# SCH_RP2040-sussybaka_2024-10-22.net
KiCad netlist of a schematic drawn in EasyEDA
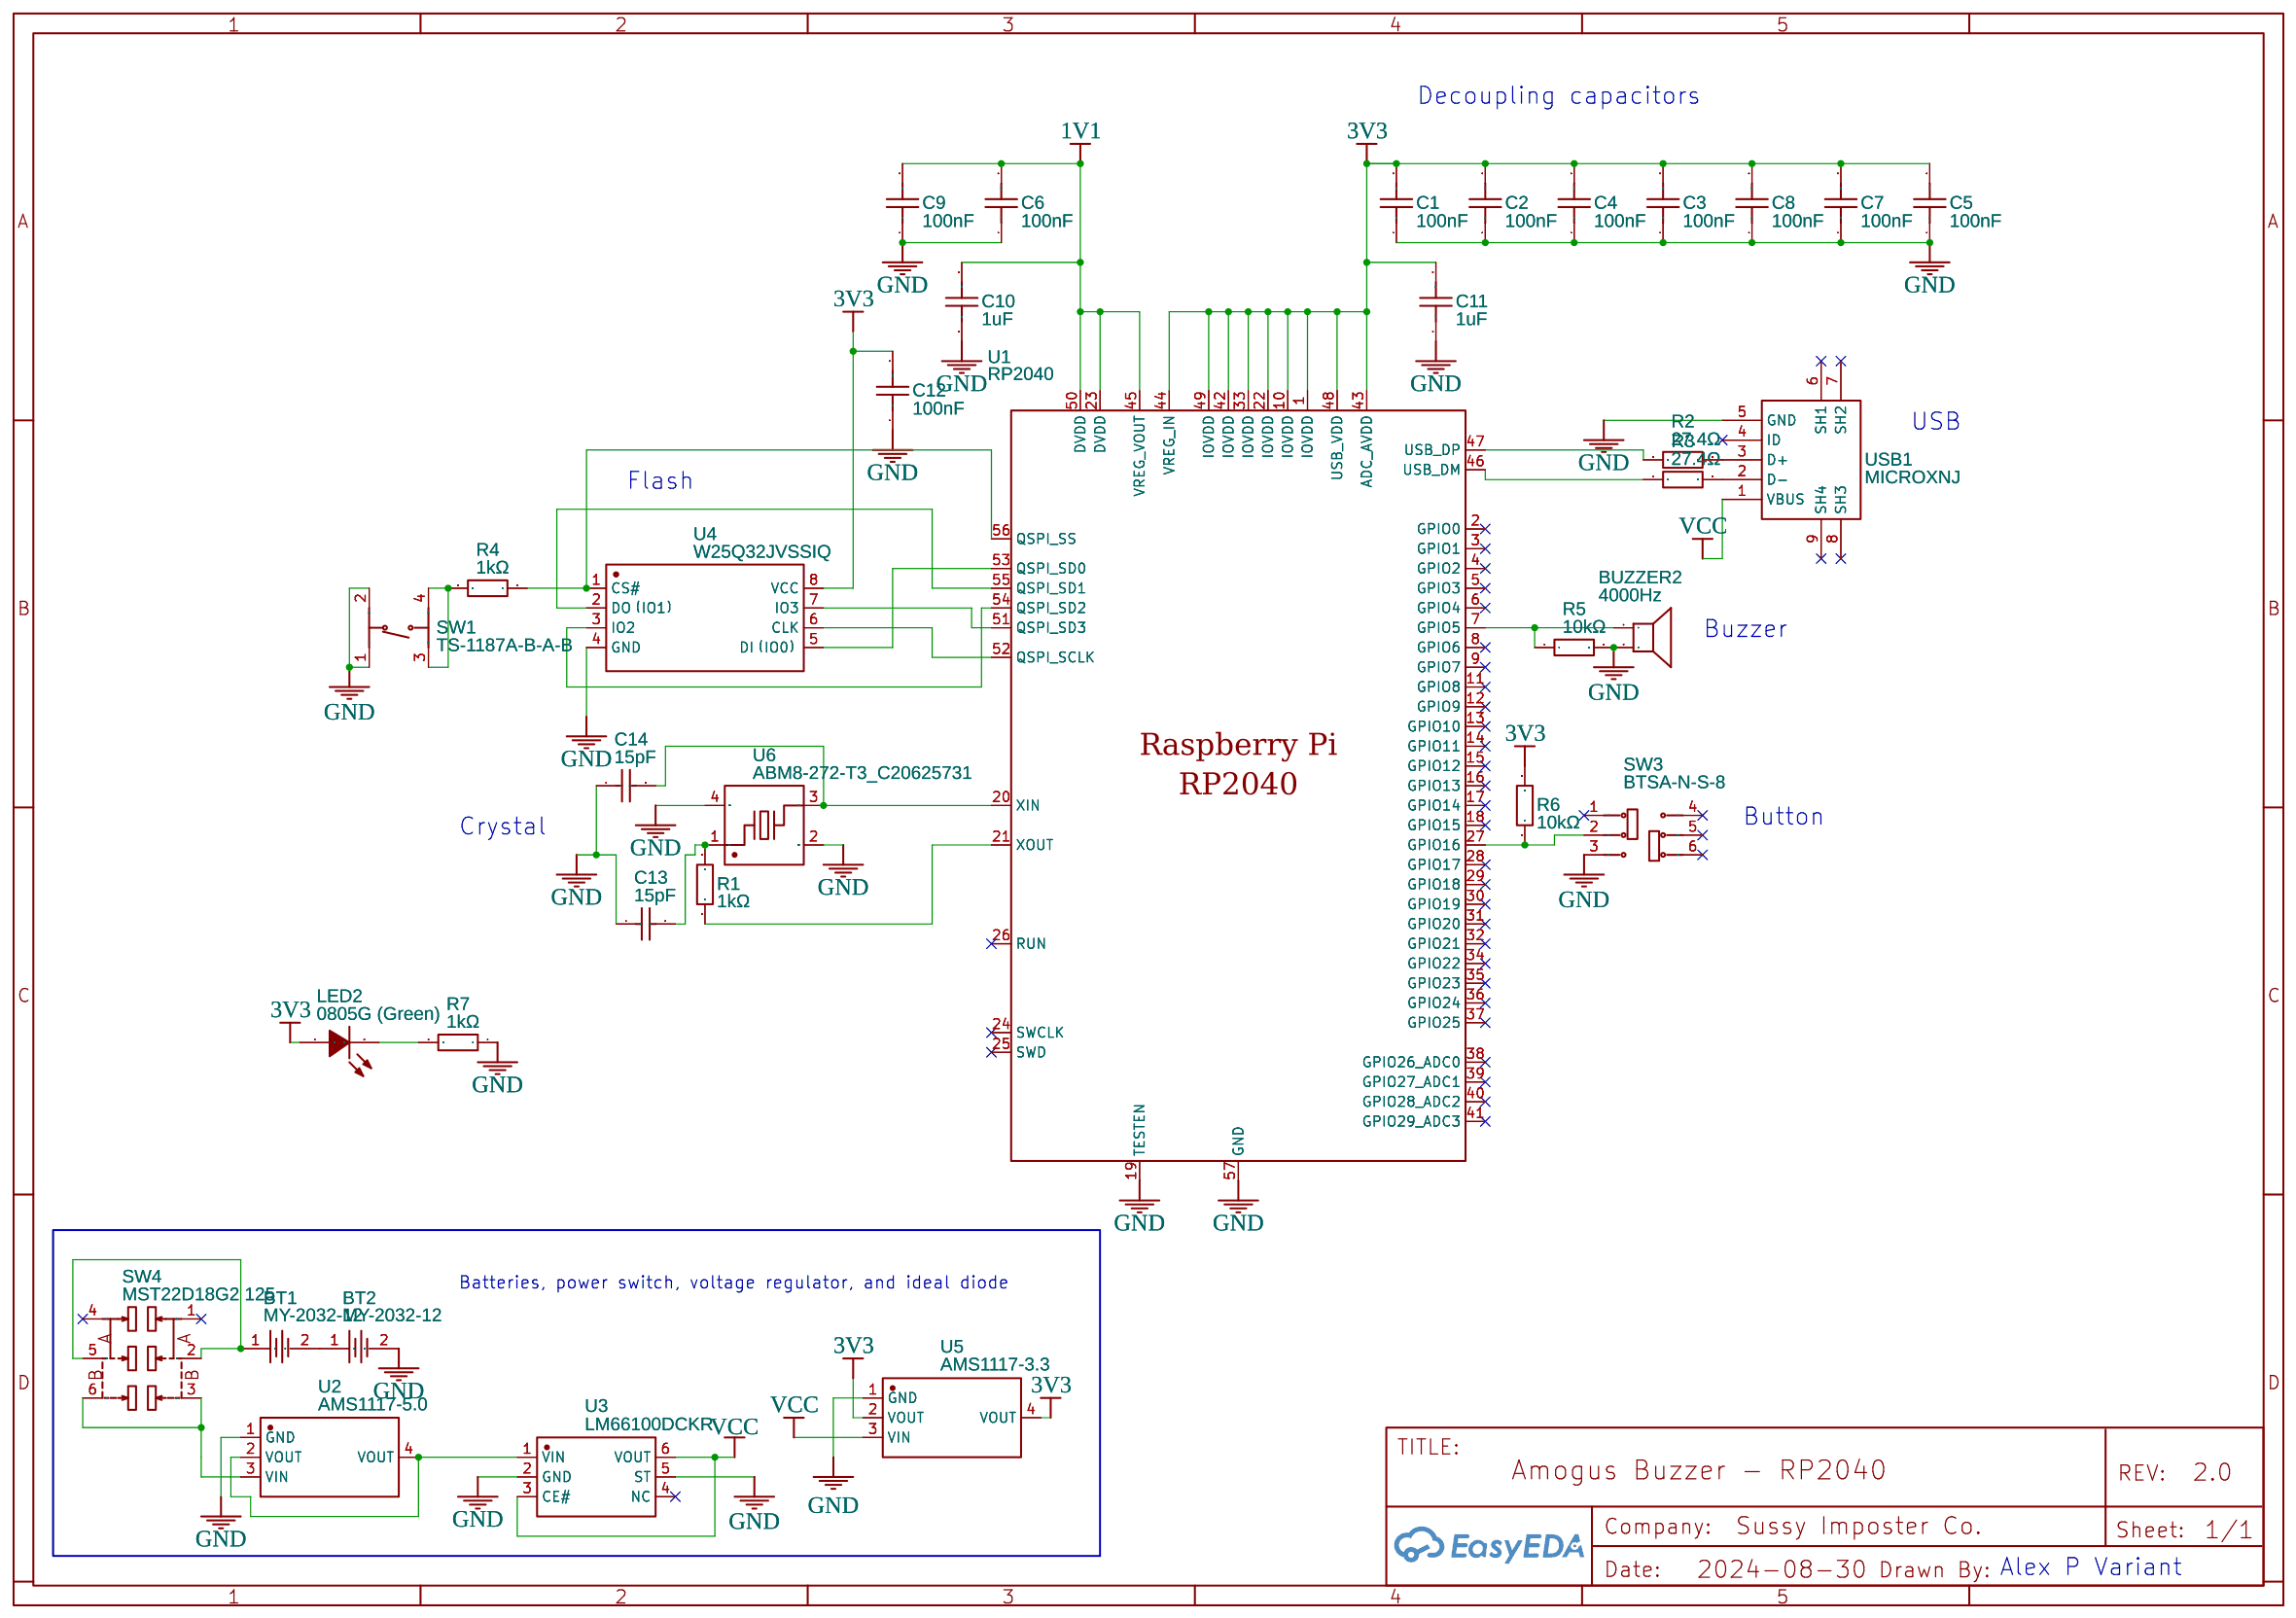
[diagram p0: schematic sheet]

(export (version "E")
  (design (tool "Eeschema 10.0.6"))
  (components
    (comp (ref "BT1")
      (value "MY-2032-12")
      (fields (field (name "Manufacturer") "MYOUNG(美阳)"))
      (libsource (lib "") (part "MY-2032-12"))
    )
    (comp (ref "BT2")
      (value "MY-2032-12")
      (fields (field (name "Manufacturer") "MYOUNG(美阳)"))
      (libsource (lib "") (part "MY-2032-12"))
    )
    (comp (ref "BUZZER2")
      (value "4000Hz")
      (fields (field (name "Manufacturer Part") "SFN-1407PA7.6") (field (name "Manufacturer") "S&S(海旭)"))
      (libsource (lib "") (part "SFN-1407PA7.6"))
    )
    (comp (ref "C1")
      (value "100nF")
      (fields
        (field (name "Manufacturer Part") "CL05B104KO5NNNC")
        (field (name "Manufacturer") "SAMSUNG(三星)")
      )
      (libsource (lib "") (part "CL05B104KO5NNNC"))
    )
    (comp (ref "C2")
      (value "100nF")
      (fields
        (field (name "Manufacturer Part") "CL05B104KO5NNNC")
        (field (name "Manufacturer") "SAMSUNG(三星)")
      )
      (libsource (lib "") (part "CL05B104KO5NNNC"))
    )
    (comp (ref "C3")
      (value "100nF")
      (fields
        (field (name "Manufacturer Part") "CL05B104KO5NNNC")
        (field (name "Manufacturer") "SAMSUNG(三星)")
      )
      (libsource (lib "") (part "CL05B104KO5NNNC"))
    )
    (comp (ref "C4")
      (value "100nF")
      (fields
        (field (name "Manufacturer Part") "CL05B104KO5NNNC")
        (field (name "Manufacturer") "SAMSUNG(三星)")
      )
      (libsource (lib "") (part "CL05B104KO5NNNC"))
    )
    (comp (ref "C5")
      (value "100nF")
      (fields
        (field (name "Manufacturer Part") "CL05B104KO5NNNC")
        (field (name "Manufacturer") "SAMSUNG(三星)")
      )
      (libsource (lib "") (part "CL05B104KO5NNNC"))
    )
    (comp (ref "C6")
      (value "100nF")
      (fields
        (field (name "Manufacturer Part") "CL05B104KO5NNNC")
        (field (name "Manufacturer") "SAMSUNG(三星)")
      )
      (libsource (lib "") (part "CL05B104KO5NNNC"))
    )
    (comp (ref "C7")
      (value "100nF")
      (fields
        (field (name "Manufacturer Part") "CL05B104KO5NNNC")
        (field (name "Manufacturer") "SAMSUNG(三星)")
      )
      (libsource (lib "") (part "CL05B104KO5NNNC"))
    )
    (comp (ref "C8")
      (value "100nF")
      (fields
        (field (name "Manufacturer Part") "CL05B104KO5NNNC")
        (field (name "Manufacturer") "SAMSUNG(三星)")
      )
      (libsource (lib "") (part "CL05B104KO5NNNC"))
    )
    (comp (ref "C9")
      (value "100nF")
      (fields
        (field (name "Manufacturer Part") "CL05B104KO5NNNC")
        (field (name "Manufacturer") "SAMSUNG(三星)")
      )
      (libsource (lib "") (part "CL05B104KO5NNNC"))
    )
    (comp (ref "C10")
      (value "1uF")
      (fields
        (field (name "Manufacturer Part") "CL10A105KB8NNNC")
        (field (name "Manufacturer") "SAMSUNG(三星)")
      )
      (libsource (lib "") (part "CL10A105KB8NNNC"))
    )
    (comp (ref "C11")
      (value "1uF")
      (fields
        (field (name "Manufacturer Part") "CL10A105KB8NNNC")
        (field (name "Manufacturer") "SAMSUNG(三星)")
      )
      (libsource (lib "") (part "CL10A105KB8NNNC"))
    )
    (comp (ref "C12")
      (value "100nF")
      (fields
        (field (name "Manufacturer Part") "CL05B104KO5NNNC")
        (field (name "Manufacturer") "SAMSUNG(三星)")
      )
      (libsource (lib "") (part "CL05B104KO5NNNC"))
    )
    (comp (ref "C13")
      (value "15pF")
      (fields (field (name "Manufacturer Part") "0402CG150J500NT") (field (name "Manufacturer") "FH(风华)"))
      (libsource (lib "") (part "0402CG150J500NT"))
    )
    (comp (ref "C14")
      (value "15pF")
      (fields (field (name "Manufacturer Part") "0402CG150J500NT") (field (name "Manufacturer") "FH(风华)"))
      (libsource (lib "") (part "0402CG150J500NT"))
    )
    (comp (ref "LED2")
      (value "0805G (Green)")
      (fields (field (name "Manufacturer Part") "KT-0805G") (field (name "Manufacturer") "KENTO"))
      (libsource (lib "") (part "0805G (Green)"))
    )
    (comp (ref "R1")
      (value "1kΩ")
      (fields
        (field (name "Manufacturer Part") "0603WAF1001T5E")
        (field (name "Manufacturer") "UNI-ROYAL(厚声)")
      )
      (libsource (lib "") (part "0603WAF1001T5E_1"))
    )
    (comp (ref "R2")
      (value "27.4Ω")
      (fields (field (name "Manufacturer Part") "ARG03FTC27R4") (field (name "Manufacturer") "Viking(光颉)"))
      (libsource (lib "") (part "ARG03FTC27R4"))
    )
    (comp (ref "R3")
      (value "27.4Ω")
      (fields (field (name "Manufacturer Part") "ARG03FTC27R4") (field (name "Manufacturer") "Viking(光颉)"))
      (libsource (lib "") (part "ARG03FTC27R4"))
    )
    (comp (ref "R4")
      (value "1kΩ")
      (fields
        (field (name "Manufacturer Part") "0603WAF1001T5E")
        (field (name "Manufacturer") "UNI-ROYAL(厚声)")
      )
      (libsource (lib "") (part "0603WAF1001T5E"))
    )
    (comp (ref "R5")
      (value "10kΩ")
      (fields
        (field (name "Manufacturer Part") "0603WAF1002T5E")
        (field (name "Manufacturer") "UNI-ROYAL(厚声)")
      )
      (libsource (lib "") (part "0603WAF1002T5E"))
    )
    (comp (ref "R6")
      (value "10kΩ")
      (fields
        (field (name "Manufacturer Part") "0603WAF1002T5E")
        (field (name "Manufacturer") "UNI-ROYAL(厚声)")
      )
      (libsource (lib "") (part "0603WAF1002T5E_1"))
    )
    (comp (ref "R7")
      (value "1kΩ")
      (fields
        (field (name "Manufacturer Part") "0603WAF1001T5E")
        (field (name "Manufacturer") "UNI-ROYAL(厚声)")
      )
      (libsource (lib "") (part "0603WAF1001T5E"))
    )
    (comp (ref "SW1")
      (value "TS-1187A-B-A-B")
      (fields (field (name "Manufacturer") "XKB Connectivity(中国星坤)"))
      (libsource (lib "") (part "TS-1187A-B-A-B"))
    )
    (comp (ref "SW3")
      (value "BTSA-N-S-8")
      (fields (field (name "Manufacturer") "ROCPU Switches(台普)"))
      (libsource (lib "") (part "BTSA-N-S-8"))
    )
    (comp (ref "SW4")
      (value "MST22D18G2 125")
      (fields (field (name "Manufacturer") "SHOU HAN(首韩)"))
      (libsource (lib "") (part "MST22D18G2 125"))
    )
    (comp (ref "U1")
      (value "RP2040")
      (fields (field (name "Manufacturer") "Raspberry Pi(树莓派)"))
      (libsource (lib "") (part "RP2040"))
    )
    (comp (ref "U2")
      (value "AMS1117-5.0")
      (fields (field (name "Manufacturer") "AMS"))
      (libsource (lib "") (part "AMS1117-5.0"))
    )
    (comp (ref "U3")
      (value "LM66100DCKR")
      (fields (field (name "Manufacturer") "TI(德州仪器)"))
      (libsource (lib "") (part "LM66100DCKR"))
    )
    (comp (ref "U4")
      (value "W25Q32JVSSIQ")
      (fields (field (name "Manufacturer") "WINBOND(华邦)"))
      (libsource (lib "") (part "W25Q32JVSSIQ"))
    )
    (comp (ref "U5")
      (value "AMS1117-3.3")
      (fields (field (name "Manufacturer") "AMS"))
      (libsource (lib "") (part "AMS1117-3.3"))
    )
    (comp (ref "U6")
      (value "ABM8-272-T3_C20625731")
      (fields (field (name "Manufacturer Part") "ABM8-272-T3") (field (name "Manufacturer") "ABRACON"))
      (libsource (lib "") (part "ABM8-272-T3_C20625731"))
    )
    (comp (ref "USB1")
      (value "MICROXNJ")
      (fields (field (name "Manufacturer Part") "MicroXNJ") (field (name "Manufacturer") "SHOU HAN(首韩)"))
      (libsource (lib "") (part "MICROXNJ"))
    )
  )
  (nets
    (net (code "1") (name "1V1") (class "Default")
      (node (ref "C10") (pin "2") (pinfunction "2_2") (pintype "unspecified"))
      (node (ref "C6") (pin "2") (pinfunction "2_2") (pintype "unspecified"))
      (node (ref "C9") (pin "2") (pinfunction "2_2") (pintype "unspecified"))
      (node (ref "U1") (pin "23") (pinfunction "DVDD_23") (pintype "bidirectional"))
      (node (ref "U1") (pin "45") (pinfunction "VREG_VOUT_45") (pintype "bidirectional"))
      (node (ref "U1") (pin "50") (pinfunction "DVDD_50") (pintype "bidirectional"))
    )
    (net (code "2") (name "3V3") (class "Default")
      (node (ref "C1") (pin "2") (pinfunction "2_2") (pintype "unspecified"))
      (node (ref "C11") (pin "2") (pinfunction "2_2") (pintype "unspecified"))
      (node (ref "C12") (pin "2") (pinfunction "2_2") (pintype "unspecified"))
      (node (ref "C2") (pin "2") (pinfunction "2_2") (pintype "unspecified"))
      (node (ref "C3") (pin "2") (pinfunction "2_2") (pintype "unspecified"))
      (node (ref "C4") (pin "2") (pinfunction "2_2") (pintype "unspecified"))
      (node (ref "C5") (pin "2") (pinfunction "2_2") (pintype "unspecified"))
      (node (ref "C7") (pin "2") (pinfunction "2_2") (pintype "unspecified"))
      (node (ref "C8") (pin "2") (pinfunction "2_2") (pintype "unspecified"))
      (node (ref "LED2") (pin "1") (pinfunction "A_1") (pintype "unspecified"))
      (node (ref "R6") (pin "2") (pinfunction "2_2") (pintype "input"))
      (node (ref "U1") (pin "1") (pinfunction "IOVDD_1") (pintype "bidirectional"))
      (node (ref "U1") (pin "10") (pinfunction "IOVDD_10") (pintype "bidirectional"))
      (node (ref "U1") (pin "22") (pinfunction "IOVDD_22") (pintype "bidirectional"))
      (node (ref "U1") (pin "33") (pinfunction "IOVDD_33") (pintype "bidirectional"))
      (node (ref "U1") (pin "42") (pinfunction "IOVDD_42") (pintype "bidirectional"))
      (node (ref "U1") (pin "43") (pinfunction "ADC_AVDD_43") (pintype "bidirectional"))
      (node (ref "U1") (pin "44") (pinfunction "VREG_IN_44") (pintype "bidirectional"))
      (node (ref "U1") (pin "48") (pinfunction "USB_VDD_48") (pintype "bidirectional"))
      (node (ref "U1") (pin "49") (pinfunction "IOVDD_49") (pintype "bidirectional"))
      (node (ref "U4") (pin "8") (pinfunction "VCC_8") (pintype "unspecified"))
      (node (ref "U5") (pin "2") (pinfunction "VOUT_2") (pintype "unspecified"))
      (node (ref "U5") (pin "4") (pinfunction "VOUT_4") (pintype "unspecified"))
    )
    (net (code "3") (name "GND") (class "Default")
      (node (ref "BT2") (pin "2") (pinfunction "2_2") (pintype "input"))
      (node (ref "BUZZER2") (pin "2") (pinfunction "2_2") (pintype "unspecified"))
      (node (ref "C1") (pin "1") (pinfunction "1_1") (pintype "unspecified"))
      (node (ref "C10") (pin "1") (pinfunction "1_1") (pintype "unspecified"))
      (node (ref "C11") (pin "1") (pinfunction "1_1") (pintype "unspecified"))
      (node (ref "C12") (pin "1") (pinfunction "1_1") (pintype "unspecified"))
      (node (ref "C13") (pin "1") (pinfunction "1_1") (pintype "input"))
      (node (ref "C14") (pin "1") (pinfunction "1_1") (pintype "input"))
      (node (ref "C2") (pin "1") (pinfunction "1_1") (pintype "unspecified"))
      (node (ref "C3") (pin "1") (pinfunction "1_1") (pintype "unspecified"))
      (node (ref "C4") (pin "1") (pinfunction "1_1") (pintype "unspecified"))
      (node (ref "C5") (pin "1") (pinfunction "1_1") (pintype "unspecified"))
      (node (ref "C6") (pin "1") (pinfunction "1_1") (pintype "unspecified"))
      (node (ref "C7") (pin "1") (pinfunction "1_1") (pintype "unspecified"))
      (node (ref "C8") (pin "1") (pinfunction "1_1") (pintype "unspecified"))
      (node (ref "C9") (pin "1") (pinfunction "1_1") (pintype "unspecified"))
      (node (ref "R5") (pin "2") (pinfunction "2_2") (pintype "input"))
      (node (ref "R7") (pin "1") (pinfunction "1_1") (pintype "input"))
      (node (ref "SW1") (pin "1") (pinfunction "A_1") (pintype "unspecified"))
      (node (ref "SW1") (pin "2") (pinfunction "B_2") (pintype "unspecified"))
      (node (ref "SW3") (pin "3") (pinfunction "3_3") (pintype "unspecified"))
      (node (ref "U1") (pin "19") (pinfunction "TESTEN_19") (pintype "unspecified"))
      (node (ref "U1") (pin "57") (pinfunction "GND_57") (pintype "bidirectional"))
      (node (ref "U2") (pin "1") (pinfunction "GND_1") (pintype "unspecified"))
      (node (ref "U3") (pin "2") (pinfunction "GND_2") (pintype "unspecified"))
      (node (ref "U3") (pin "5") (pinfunction "ST_5") (pintype "unspecified"))
      (node (ref "U4") (pin "4") (pinfunction "GND_4") (pintype "unspecified"))
      (node (ref "U5") (pin "1") (pinfunction "GND_1") (pintype "unspecified"))
      (node (ref "U6") (pin "2") (pinfunction "GND_2") (pintype "input"))
      (node (ref "U6") (pin "4") (pinfunction "GND_4") (pintype "input"))
      (node (ref "USB1") (pin "5") (pinfunction "GND_5") (pintype "unspecified"))
    )
    (net (code "4") (name "Net-(BT1-Pad1)") (class "Default")
      (node (ref "BT1") (pin "1") (pinfunction "1_1") (pintype "input"))
      (node (ref "SW4") (pin "2") (pinfunction "2_2") (pintype "unspecified"))
      (node (ref "SW4") (pin "5") (pinfunction "5_5") (pintype "unspecified"))
    )
    (net (code "5") (name "Net-(BT1-Pad2)") (class "Default")
      (node (ref "BT1") (pin "2") (pinfunction "2_2") (pintype "input"))
      (node (ref "BT2") (pin "1") (pinfunction "1_1") (pintype "input"))
    )
    (net (code "6") (name "Net-(C13-Pad2)") (class "Default")
      (node (ref "C13") (pin "2") (pinfunction "2_2") (pintype "input"))
      (node (ref "R1") (pin "2") (pinfunction "2_2") (pintype "input"))
      (node (ref "U6") (pin "1") (pinfunction "1_1") (pintype "input"))
    )
    (net (code "7") (name "Net-(LED2-K)") (class "Default")
      (node (ref "LED2") (pin "2") (pinfunction "K_2") (pintype "unspecified"))
      (node (ref "R7") (pin "2") (pinfunction "2_2") (pintype "input"))
    )
    (net (code "8") (name "Net-(SW1-C)") (class "Default")
      (node (ref "R4") (pin "2") (pinfunction "2_2") (pintype "input"))
      (node (ref "SW1") (pin "3") (pinfunction "C_3") (pintype "unspecified"))
      (node (ref "SW1") (pin "4") (pinfunction "D_4") (pintype "unspecified"))
    )
    (net (code "9") (name "Net-(U1-GPIO5)") (class "Default")
      (node (ref "BUZZER2") (pin "1") (pinfunction "1_1") (pintype "unspecified"))
      (node (ref "R5") (pin "1") (pinfunction "1_1") (pintype "input"))
      (node (ref "U1") (pin "7") (pinfunction "GPIO5_7") (pintype "bidirectional"))
    )
    (net (code "10") (name "Net-(U1-GPIO16)") (class "Default")
      (node (ref "R6") (pin "1") (pinfunction "1_1") (pintype "input"))
      (node (ref "SW3") (pin "2") (pinfunction "2_2") (pintype "unspecified"))
      (node (ref "U1") (pin "27") (pinfunction "GPIO16_27") (pintype "bidirectional"))
    )
    (net (code "11") (name "Net-(U1-QSPI_SCLK)") (class "Default")
      (node (ref "U1") (pin "52") (pinfunction "QSPI_SCLK_52") (pintype "output"))
      (node (ref "U4") (pin "6") (pinfunction "CLK_6") (pintype "unspecified"))
    )
    (net (code "12") (name "Net-(U1-QSPI_SD0)") (class "Default")
      (node (ref "U1") (pin "53") (pinfunction "QSPI_SD0_53") (pintype "bidirectional"))
      (node (ref "U4") (pin "5") (pinfunction "DI（IO0）_5") (pintype "unspecified"))
    )
    (net (code "13") (name "Net-(U1-QSPI_SD1)") (class "Default")
      (node (ref "U1") (pin "55") (pinfunction "QSPI_SD1_55") (pintype "bidirectional"))
      (node (ref "U4") (pin "2") (pinfunction "DO（IO1）_2") (pintype "unspecified"))
    )
    (net (code "14") (name "Net-(U1-QSPI_SD2)") (class "Default")
      (node (ref "U1") (pin "54") (pinfunction "QSPI_SD2_54") (pintype "bidirectional"))
      (node (ref "U4") (pin "3") (pinfunction "IO2_3") (pintype "unspecified"))
    )
    (net (code "15") (name "Net-(U1-QSPI_SD3)") (class "Default")
      (node (ref "U1") (pin "51") (pinfunction "QSPI_SD3_51") (pintype "bidirectional"))
      (node (ref "U4") (pin "7") (pinfunction "IO3_7") (pintype "unspecified"))
    )
    (net (code "16") (name "Net-(U1-QSPI_SS)") (class "Default")
      (node (ref "R4") (pin "1") (pinfunction "1_1") (pintype "input"))
      (node (ref "U1") (pin "56") (pinfunction "QSPI_SS_56") (pintype "bidirectional"))
      (node (ref "U4") (pin "1") (pinfunction "CS#_1") (pintype "unspecified"))
    )
    (net (code "17") (name "Net-(U1-USB_DM)") (class "Default")
      (node (ref "R3") (pin "1") (pinfunction "1_1") (pintype "unspecified"))
      (node (ref "U1") (pin "46") (pinfunction "USB_DM_46") (pintype "bidirectional"))
    )
    (net (code "18") (name "Net-(U1-USB_DP)") (class "Default")
      (node (ref "R2") (pin "1") (pinfunction "1_1") (pintype "unspecified"))
      (node (ref "U1") (pin "47") (pinfunction "USB_DP_47") (pintype "bidirectional"))
    )
    (net (code "19") (name "Net-(U1-XIN)") (class "Default")
      (node (ref "C14") (pin "2") (pinfunction "2_2") (pintype "input"))
      (node (ref "U1") (pin "20") (pinfunction "XIN_20") (pintype "input"))
      (node (ref "U6") (pin "3") (pinfunction "3_3") (pintype "input"))
    )
    (net (code "20") (name "Net-(U1-XOUT)") (class "Default")
      (node (ref "R1") (pin "1") (pinfunction "1_1") (pintype "input"))
      (node (ref "U1") (pin "21") (pinfunction "XOUT_21") (pintype "unspecified"))
    )
    (net (code "21") (name "Net-(U2-VIN)") (class "Default")
      (node (ref "SW4") (pin "3") (pinfunction "3_3") (pintype "unspecified"))
      (node (ref "SW4") (pin "6") (pinfunction "6_6") (pintype "unspecified"))
      (node (ref "U2") (pin "3") (pinfunction "VIN_3") (pintype "unspecified"))
    )
    (net (code "22") (name "Net-(U3-VIN)") (class "Default")
      (node (ref "U2") (pin "2") (pinfunction "VOUT_2") (pintype "unspecified"))
      (node (ref "U2") (pin "4") (pinfunction "VOUT_4") (pintype "unspecified"))
      (node (ref "U3") (pin "1") (pinfunction "VIN_1") (pintype "unspecified"))
    )
    (net (code "23") (name "Net-(USB1-D+)") (class "Default")
      (node (ref "R2") (pin "2") (pinfunction "2_2") (pintype "unspecified"))
      (node (ref "USB1") (pin "3") (pinfunction "D+_3") (pintype "unspecified"))
    )
    (net (code "24") (name "Net-(USB1-D-)") (class "Default")
      (node (ref "R3") (pin "2") (pinfunction "2_2") (pintype "unspecified"))
      (node (ref "USB1") (pin "2") (pinfunction "D-_2") (pintype "unspecified"))
    )
    (net (code "25") (name "VCC") (class "Default")
      (node (ref "U3") (pin "3") (pinfunction "CE#_3") (pintype "unspecified"))
      (node (ref "U3") (pin "6") (pinfunction "VOUT_6") (pintype "unspecified"))
      (node (ref "U5") (pin "3") (pinfunction "VIN_3") (pintype "unspecified"))
      (node (ref "USB1") (pin "1") (pinfunction "VBUS_1") (pintype "unspecified"))
    )
    (net (code "26") (name "unconnected-(SW3-Pad1)") (class "Default")
      (node (ref "SW3") (pin "1") (pinfunction "1_1") (pintype "unspecified+no_connect"))
    )
    (net (code "27") (name "unconnected-(SW3-Pad4)") (class "Default")
      (node (ref "SW3") (pin "4") (pinfunction "4_4") (pintype "unspecified+no_connect"))
    )
    (net (code "28") (name "unconnected-(SW3-Pad5)") (class "Default")
      (node (ref "SW3") (pin "5") (pinfunction "5_5") (pintype "unspecified+no_connect"))
    )
    (net (code "29") (name "unconnected-(SW3-Pad6)") (class "Default")
      (node (ref "SW3") (pin "6") (pinfunction "6_6") (pintype "unspecified+no_connect"))
    )
    (net (code "30") (name "unconnected-(SW4-Pad1)") (class "Default")
      (node (ref "SW4") (pin "1") (pinfunction "1_1") (pintype "unspecified+no_connect"))
    )
    (net (code "31") (name "unconnected-(SW4-Pad4)") (class "Default")
      (node (ref "SW4") (pin "4") (pinfunction "4_4") (pintype "unspecified+no_connect"))
    )
    (net (code "32") (name "unconnected-(U1-GPIO0-Pad2)") (class "Default")
      (node (ref "U1") (pin "2") (pinfunction "GPIO0_2") (pintype "bidirectional+no_connect"))
    )
    (net (code "33") (name "unconnected-(U1-GPIO1-Pad3)") (class "Default")
      (node (ref "U1") (pin "3") (pinfunction "GPIO1_3") (pintype "bidirectional+no_connect"))
    )
    (net (code "34") (name "unconnected-(U1-GPIO2-Pad4)") (class "Default")
      (node (ref "U1") (pin "4") (pinfunction "GPIO2_4") (pintype "bidirectional+no_connect"))
    )
    (net (code "35") (name "unconnected-(U1-GPIO3-Pad5)") (class "Default")
      (node (ref "U1") (pin "5") (pinfunction "GPIO3_5") (pintype "bidirectional+no_connect"))
    )
    (net (code "36") (name "unconnected-(U1-GPIO4-Pad6)") (class "Default")
      (node (ref "U1") (pin "6") (pinfunction "GPIO4_6") (pintype "bidirectional+no_connect"))
    )
    (net (code "37") (name "unconnected-(U1-GPIO6-Pad8)") (class "Default")
      (node (ref "U1") (pin "8") (pinfunction "GPIO6_8") (pintype "bidirectional+no_connect"))
    )
    (net (code "38") (name "unconnected-(U1-GPIO7-Pad9)") (class "Default")
      (node (ref "U1") (pin "9") (pinfunction "GPIO7_9") (pintype "bidirectional+no_connect"))
    )
    (net (code "39") (name "unconnected-(U1-GPIO8-Pad11)") (class "Default")
      (node (ref "U1") (pin "11") (pinfunction "GPIO8_11") (pintype "bidirectional+no_connect"))
    )
    (net (code "40") (name "unconnected-(U1-GPIO9-Pad12)") (class "Default")
      (node (ref "U1") (pin "12") (pinfunction "GPIO9_12") (pintype "bidirectional+no_connect"))
    )
    (net (code "41") (name "unconnected-(U1-GPIO10-Pad13)") (class "Default")
      (node (ref "U1") (pin "13") (pinfunction "GPIO10_13") (pintype "bidirectional+no_connect"))
    )
    (net (code "42") (name "unconnected-(U1-GPIO11-Pad14)") (class "Default")
      (node (ref "U1") (pin "14") (pinfunction "GPIO11_14") (pintype "bidirectional+no_connect"))
    )
    (net (code "43") (name "unconnected-(U1-GPIO12-Pad15)") (class "Default")
      (node (ref "U1") (pin "15") (pinfunction "GPIO12_15") (pintype "bidirectional+no_connect"))
    )
    (net (code "44") (name "unconnected-(U1-GPIO13-Pad16)") (class "Default")
      (node (ref "U1") (pin "16") (pinfunction "GPIO13_16") (pintype "bidirectional+no_connect"))
    )
    (net (code "45") (name "unconnected-(U1-GPIO14-Pad17)") (class "Default")
      (node (ref "U1") (pin "17") (pinfunction "GPIO14_17") (pintype "bidirectional+no_connect"))
    )
    (net (code "46") (name "unconnected-(U1-GPIO15-Pad18)") (class "Default")
      (node (ref "U1") (pin "18") (pinfunction "GPIO15_18") (pintype "bidirectional+no_connect"))
    )
    (net (code "47") (name "unconnected-(U1-GPIO17-Pad28)") (class "Default")
      (node (ref "U1") (pin "28") (pinfunction "GPIO17_28") (pintype "bidirectional+no_connect"))
    )
    (net (code "48") (name "unconnected-(U1-GPIO18-Pad29)") (class "Default")
      (node (ref "U1") (pin "29") (pinfunction "GPIO18_29") (pintype "bidirectional+no_connect"))
    )
    (net (code "49") (name "unconnected-(U1-GPIO19-Pad30)") (class "Default")
      (node (ref "U1") (pin "30") (pinfunction "GPIO19_30") (pintype "bidirectional+no_connect"))
    )
    (net (code "50") (name "unconnected-(U1-GPIO20-Pad31)") (class "Default")
      (node (ref "U1") (pin "31") (pinfunction "GPIO20_31") (pintype "bidirectional+no_connect"))
    )
    (net (code "51") (name "unconnected-(U1-GPIO21-Pad32)") (class "Default")
      (node (ref "U1") (pin "32") (pinfunction "GPIO21_32") (pintype "bidirectional+no_connect"))
    )
    (net (code "52") (name "unconnected-(U1-GPIO22-Pad34)") (class "Default")
      (node (ref "U1") (pin "34") (pinfunction "GPIO22_34") (pintype "bidirectional+no_connect"))
    )
    (net (code "53") (name "unconnected-(U1-GPIO23-Pad35)") (class "Default")
      (node (ref "U1") (pin "35") (pinfunction "GPIO23_35") (pintype "bidirectional+no_connect"))
    )
    (net (code "54") (name "unconnected-(U1-GPIO24-Pad36)") (class "Default")
      (node (ref "U1") (pin "36") (pinfunction "GPIO24_36") (pintype "bidirectional+no_connect"))
    )
    (net (code "55") (name "unconnected-(U1-GPIO25-Pad37)") (class "Default")
      (node (ref "U1") (pin "37") (pinfunction "GPIO25_37") (pintype "bidirectional+no_connect"))
    )
    (net (code "56") (name "unconnected-(U1-GPIO26_ADC0-Pad38)") (class "Default")
      (node (ref "U1") (pin "38") (pinfunction "GPIO26_ADC0_38") (pintype "bidirectional+no_connect"))
    )
    (net (code "57") (name "unconnected-(U1-GPIO27_ADC1-Pad39)") (class "Default")
      (node (ref "U1") (pin "39") (pinfunction "GPIO27_ADC1_39") (pintype "bidirectional+no_connect"))
    )
    (net (code "58") (name "unconnected-(U1-GPIO28_ADC2-Pad40)") (class "Default")
      (node (ref "U1") (pin "40") (pinfunction "GPIO28_ADC2_40") (pintype "bidirectional+no_connect"))
    )
    (net (code "59") (name "unconnected-(U1-GPIO29_ADC3-Pad41)") (class "Default")
      (node (ref "U1") (pin "41") (pinfunction "GPIO29_ADC3_41") (pintype "bidirectional+no_connect"))
    )
    (net (code "60") (name "unconnected-(U1-RUN-Pad26)") (class "Default")
      (node (ref "U1") (pin "26") (pinfunction "RUN_26") (pintype "input+no_connect"))
    )
    (net (code "61") (name "unconnected-(U1-SWCLK-Pad24)") (class "Default")
      (node (ref "U1") (pin "24") (pinfunction "SWCLK_24") (pintype "output+no_connect"))
    )
    (net (code "62") (name "unconnected-(U1-SWD-Pad25)") (class "Default")
      (node (ref "U1") (pin "25") (pinfunction "SWD_25") (pintype "bidirectional+no_connect"))
    )
    (net (code "63") (name "unconnected-(U3-NC-Pad4)") (class "Default")
      (node (ref "U3") (pin "4") (pinfunction "NC_4") (pintype "unspecified+no_connect"))
    )
    (net (code "64") (name "unconnected-(USB1-ID-Pad4)") (class "Default")
      (node (ref "USB1") (pin "4") (pinfunction "ID_4") (pintype "unspecified+no_connect"))
    )
    (net (code "65") (name "unconnected-(USB1-SH1-Pad6)") (class "Default")
      (node (ref "USB1") (pin "6") (pinfunction "SH1_6") (pintype "unspecified+no_connect"))
    )
    (net (code "66") (name "unconnected-(USB1-SH2-Pad7)") (class "Default")
      (node (ref "USB1") (pin "7") (pinfunction "SH2_7") (pintype "unspecified+no_connect"))
    )
    (net (code "67") (name "unconnected-(USB1-SH3-Pad8)") (class "Default")
      (node (ref "USB1") (pin "8") (pinfunction "SH3_8") (pintype "unspecified+no_connect"))
    )
    (net (code "68") (name "unconnected-(USB1-SH4-Pad9)") (class "Default")
      (node (ref "USB1") (pin "9") (pinfunction "SH4_9") (pintype "unspecified+no_connect"))
    )
  )
)
